# treehopper-fob.net
KiCad netlist of a schematic drawn in Altium Designer
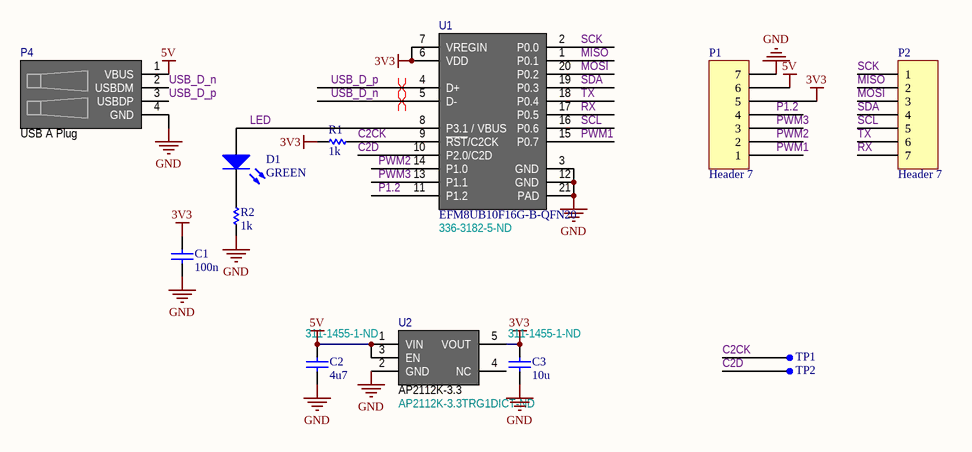
[diagram p0: treehopper-fob.SchDoc]

(export (version "E")
  (design (tool "Eeschema 10.0.6"))
  (components
    (comp (ref "C1")
      (value "100n")
      (footprint "CAPC1005N")
      (description "Capacitor (Semiconductor SIM Model)")
      (fields (field (name "PUBLISHER") "Altium Limited"))
      (libsource (lib "Miscellaneous Devices") (part "Cap Semi"))
    )
    (comp (ref "C2")
      (value "4u7")
      (footprint "CAPC1608N")
      (description "CAP SEMI 4U7 10V 0603")
      (fields
        (field (name "SUPPLIER PART NUMBER 1") "311-1455-1-ND")
        (field (name "PUBLISHER") "Altium Limited")
      )
      (libsource (lib "Miscellaneous Devices") (part "Cap Semi"))
    )
    (comp (ref "C3")
      (value "10u")
      (footprint "CAPC1608N")
      (description "CAP SEMI 4U7 10V 0603")
      (fields
        (field (name "SUPPLIER PART NUMBER 1") "311-1455-1-ND")
        (field (name "PUBLISHER") "Altium Limited")
      )
      (libsource (lib "Miscellaneous Devices") (part "Cap Semi"))
    )
    (comp (ref "D1")
      (value "GREEN")
      (footprint "LTST-C190GKT_NO_SILK")
      (description "Typical greenGaAs LED")
      (fields (field (name "PUBLISHER") "Altium Limited"))
      (libsource (lib "Miscellaneous Devices") (part "LED_GREEN"))
    )
    (comp (ref "P1")
      (value "Header 7")
      (footprint "HDR1X7_CASTELATED")
      (description "Header, 7-Pin")
      (fields (field (name "PUBLISHER") "Altium Limited"))
      (libsource (lib "") (part "Header 7_1"))
    )
    (comp (ref "P2")
      (value "Header 7")
      (footprint "HDR1X7_CASTELATED")
      (description "Header, 7-Pin")
      (fields (field (name "PUBLISHER") "Altium Limited"))
      (libsource (lib "Miscellaneous Connectors") (part "Header 7"))
    )
    (comp (ref "P4")
      (value "USB A Plug")
      (footprint "USB/SM2.5-4H4_NOSILK")
      (libsource (lib "Miscellaneous Connectors") (part "USB A Plug"))
    )
    (comp (ref "R1")
      (value "1k")
      (footprint "RESC1005N")
      (description "Semiconductor Resistor")
      (fields (field (name "PUBLISHER") "Altium Limited"))
      (libsource (lib "Miscellaneous Devices") (part "Res Semi"))
    )
    (comp (ref "R2")
      (value "1k")
      (footprint "RESC1005N")
      (description "Semiconductor Resistor")
      (fields (field (name "PUBLISHER") "Altium Limited"))
      (libsource (lib "Miscellaneous Devices") (part "Res Semi"))
    )
    (comp (ref "TP1")
      (value "TESTPOINT")
      (footprint "TESTPOINT100")
      (description "Testpoint")
      (fields (field (name "PUBLISHER") "Altium Limited"))
      (libsource (lib "Miscellaneous Connectors") (part "TESTPOINT"))
    )
    (comp (ref "TP2")
      (value "TESTPOINT")
      (footprint "TESTPOINT100")
      (description "Testpoint")
      (fields (field (name "PUBLISHER") "Altium Limited"))
      (libsource (lib "Miscellaneous Connectors") (part "TESTPOINT"))
    )
    (comp (ref "U1")
      (value "EFM8UB10F16G-B-QFN20")
      (footprint "QFN50P300X300X90-20N-NO-SILK")
      (description "IC MCU 16KB 20QFN")
      (fields
        (field (name "MANUFACTURER") "Silicon Labs")
        (field (name "SUPPLIER PART NUMBER 1") "336-3182-5-ND")
      )
      (libsource (lib "SiLabs EFM8 MCU") (part "EFM8UB10F16G-B-QFN20"))
    )
    (comp (ref "U2")
      (value "AP2112K-3.3")
      (footprint "SOT23-5AN-no-silk")
      (description "AP2112 IC REG LDO 3.3V 0.6A SOT25")
      (fields
        (field (name "MANUFACTURER") "Diodes Incorporated")
        (field (name "MANUFACTURER PART NUMBER") "AP2112K-3.3TRG1")
        (field (name "SUPPLIER PART NUMBER 1") "AP2112K-3.3TRG1DICT-ND")
      )
      (libsource (lib "Diodes Inc LDO Regulator") (part "AP2112K-3.3"))
    )
  )
  (nets
    (net (code "1") (name "/C2CK") (class "Default")
      (node (ref "R1") (pin "1") (pinfunction "1_1") (pintype "passive"))
      (node (ref "TP1") (pin "1") (pinfunction "TP_1") (pintype "passive"))
      (node (ref "U1") (pin "9") (pinfunction "~{RST}/C2CK_9") (pintype "passive"))
    )
    (net (code "2") (name "/C2D") (class "Default")
      (node (ref "TP2") (pin "1") (pinfunction "TP_1") (pintype "passive"))
      (node (ref "U1") (pin "10") (pinfunction "P2.0/C2D_10") (pintype "passive"))
    )
    (net (code "3") (name "/LED") (class "Default")
      (node (ref "D1") (pin "1") (pinfunction "A_1") (pintype "passive"))
      (node (ref "U1") (pin "8") (pinfunction "P3.1_/_VBUS_8") (pintype "passive"))
    )
    (net (code "4") (name "/MISO") (class "Default")
      (node (ref "P2") (pin "2") (pinfunction "2_2") (pintype "passive"))
      (node (ref "U1") (pin "1") (pinfunction "P0.1_1") (pintype "passive"))
    )
    (net (code "5") (name "/MOSI") (class "Default")
      (node (ref "P2") (pin "3") (pinfunction "3_3") (pintype "passive"))
      (node (ref "U1") (pin "20") (pinfunction "P0.2_20") (pintype "passive"))
    )
    (net (code "6") (name "/P1.2") (class "Default")
      (node (ref "P1") (pin "4") (pinfunction "4_4") (pintype "passive"))
      (node (ref "U1") (pin "11") (pinfunction "P1.2_11") (pintype "passive"))
    )
    (net (code "7") (name "/PWM1") (class "Default")
      (node (ref "P1") (pin "1") (pinfunction "1_1") (pintype "passive"))
      (node (ref "U1") (pin "15") (pinfunction "P0.7_15") (pintype "passive"))
    )
    (net (code "8") (name "/PWM2") (class "Default")
      (node (ref "P1") (pin "2") (pinfunction "2_2") (pintype "passive"))
      (node (ref "U1") (pin "14") (pinfunction "P1.0_14") (pintype "passive"))
    )
    (net (code "9") (name "/PWM3") (class "Default")
      (node (ref "P1") (pin "3") (pinfunction "3_3") (pintype "passive"))
      (node (ref "U1") (pin "13") (pinfunction "P1.1_13") (pintype "passive"))
    )
    (net (code "10") (name "/RX") (class "Default")
      (node (ref "P2") (pin "7") (pinfunction "7_7") (pintype "passive"))
      (node (ref "U1") (pin "17") (pinfunction "P0.5_17") (pintype "passive"))
    )
    (net (code "11") (name "/SCK") (class "Default")
      (node (ref "P2") (pin "1") (pinfunction "1_1") (pintype "passive"))
      (node (ref "U1") (pin "2") (pinfunction "P0.0_2") (pintype "passive"))
    )
    (net (code "12") (name "/SCL") (class "Default")
      (node (ref "P2") (pin "5") (pinfunction "5_5") (pintype "passive"))
      (node (ref "U1") (pin "16") (pinfunction "P0.6_16") (pintype "passive"))
    )
    (net (code "13") (name "/SDA") (class "Default")
      (node (ref "P2") (pin "4") (pinfunction "4_4") (pintype "passive"))
      (node (ref "U1") (pin "19") (pinfunction "P0.3_19") (pintype "passive"))
    )
    (net (code "14") (name "/TX") (class "Default")
      (node (ref "P2") (pin "6") (pinfunction "6_6") (pintype "passive"))
      (node (ref "U1") (pin "18") (pinfunction "P0.4_18") (pintype "passive"))
    )
    (net (code "15") (name "/USB_D_n") (class "Default")
      (node (ref "P4") (pin "2") (pinfunction "USBDM_2") (pintype "power_in"))
      (node (ref "U1") (pin "5") (pinfunction "D-_5") (pintype "passive"))
    )
    (net (code "16") (name "/USB_D_p") (class "Default")
      (node (ref "P4") (pin "3") (pinfunction "USBDP_3") (pintype "power_in"))
      (node (ref "U1") (pin "4") (pinfunction "D+_4") (pintype "passive"))
    )
    (net (code "17") (name "3V3") (class "Default")
      (node (ref "C1") (pin "2") (pinfunction "2_2") (pintype "passive"))
      (node (ref "C3") (pin "2") (pinfunction "2_2") (pintype "passive"))
      (node (ref "P1") (pin "5") (pinfunction "5_5") (pintype "passive"))
      (node (ref "R1") (pin "2") (pinfunction "2_2") (pintype "passive"))
      (node (ref "U1") (pin "6") (pinfunction "VDD_6") (pintype "passive"))
      (node (ref "U1") (pin "7") (pinfunction "VREGIN_7") (pintype "passive"))
      (node (ref "U2") (pin "5") (pinfunction "VOUT_5") (pintype "passive"))
    )
    (net (code "18") (name "5V") (class "Default")
      (node (ref "C2") (pin "2") (pinfunction "2_2") (pintype "passive"))
      (node (ref "P1") (pin "6") (pinfunction "6_6") (pintype "passive"))
      (node (ref "P4") (pin "1") (pinfunction "VBUS_1") (pintype "power_in"))
      (node (ref "U2") (pin "1") (pinfunction "VIN_1") (pintype "passive"))
      (node (ref "U2") (pin "3") (pinfunction "EN_3") (pintype "passive"))
    )
    (net (code "19") (name "GND") (class "Default")
      (node (ref "C1") (pin "1") (pinfunction "1_1") (pintype "passive"))
      (node (ref "C2") (pin "1") (pinfunction "1_1") (pintype "passive"))
      (node (ref "C3") (pin "1") (pinfunction "1_1") (pintype "passive"))
      (node (ref "P1") (pin "7") (pinfunction "7_7") (pintype "passive"))
      (node (ref "P4") (pin "4") (pinfunction "GND_4") (pintype "power_in"))
      (node (ref "R2") (pin "1") (pinfunction "1_1") (pintype "passive"))
      (node (ref "U1") (pin "12") (pinfunction "GND_12") (pintype "passive"))
      (node (ref "U1") (pin "21") (pinfunction "PAD_21") (pintype "passive"))
      (node (ref "U1") (pin "3") (pinfunction "GND_3") (pintype "passive"))
      (node (ref "U2") (pin "2") (pinfunction "GND_2") (pintype "passive"))
    )
    (net (code "20") (name "Net-(D1-K)") (class "Default")
      (node (ref "D1") (pin "2") (pinfunction "K_2") (pintype "passive"))
      (node (ref "R2") (pin "2") (pinfunction "2_2") (pintype "passive"))
    )
    (net (code "21") (name "unconnected-(U2-NC-Pad4)") (class "Default")
      (node (ref "U2") (pin "4") (pinfunction "NC_4") (pintype "passive"))
    )
  )
)
